# Capteur_Main_Droite.net
KiCad netlist of a schematic drawn in EasyEDA
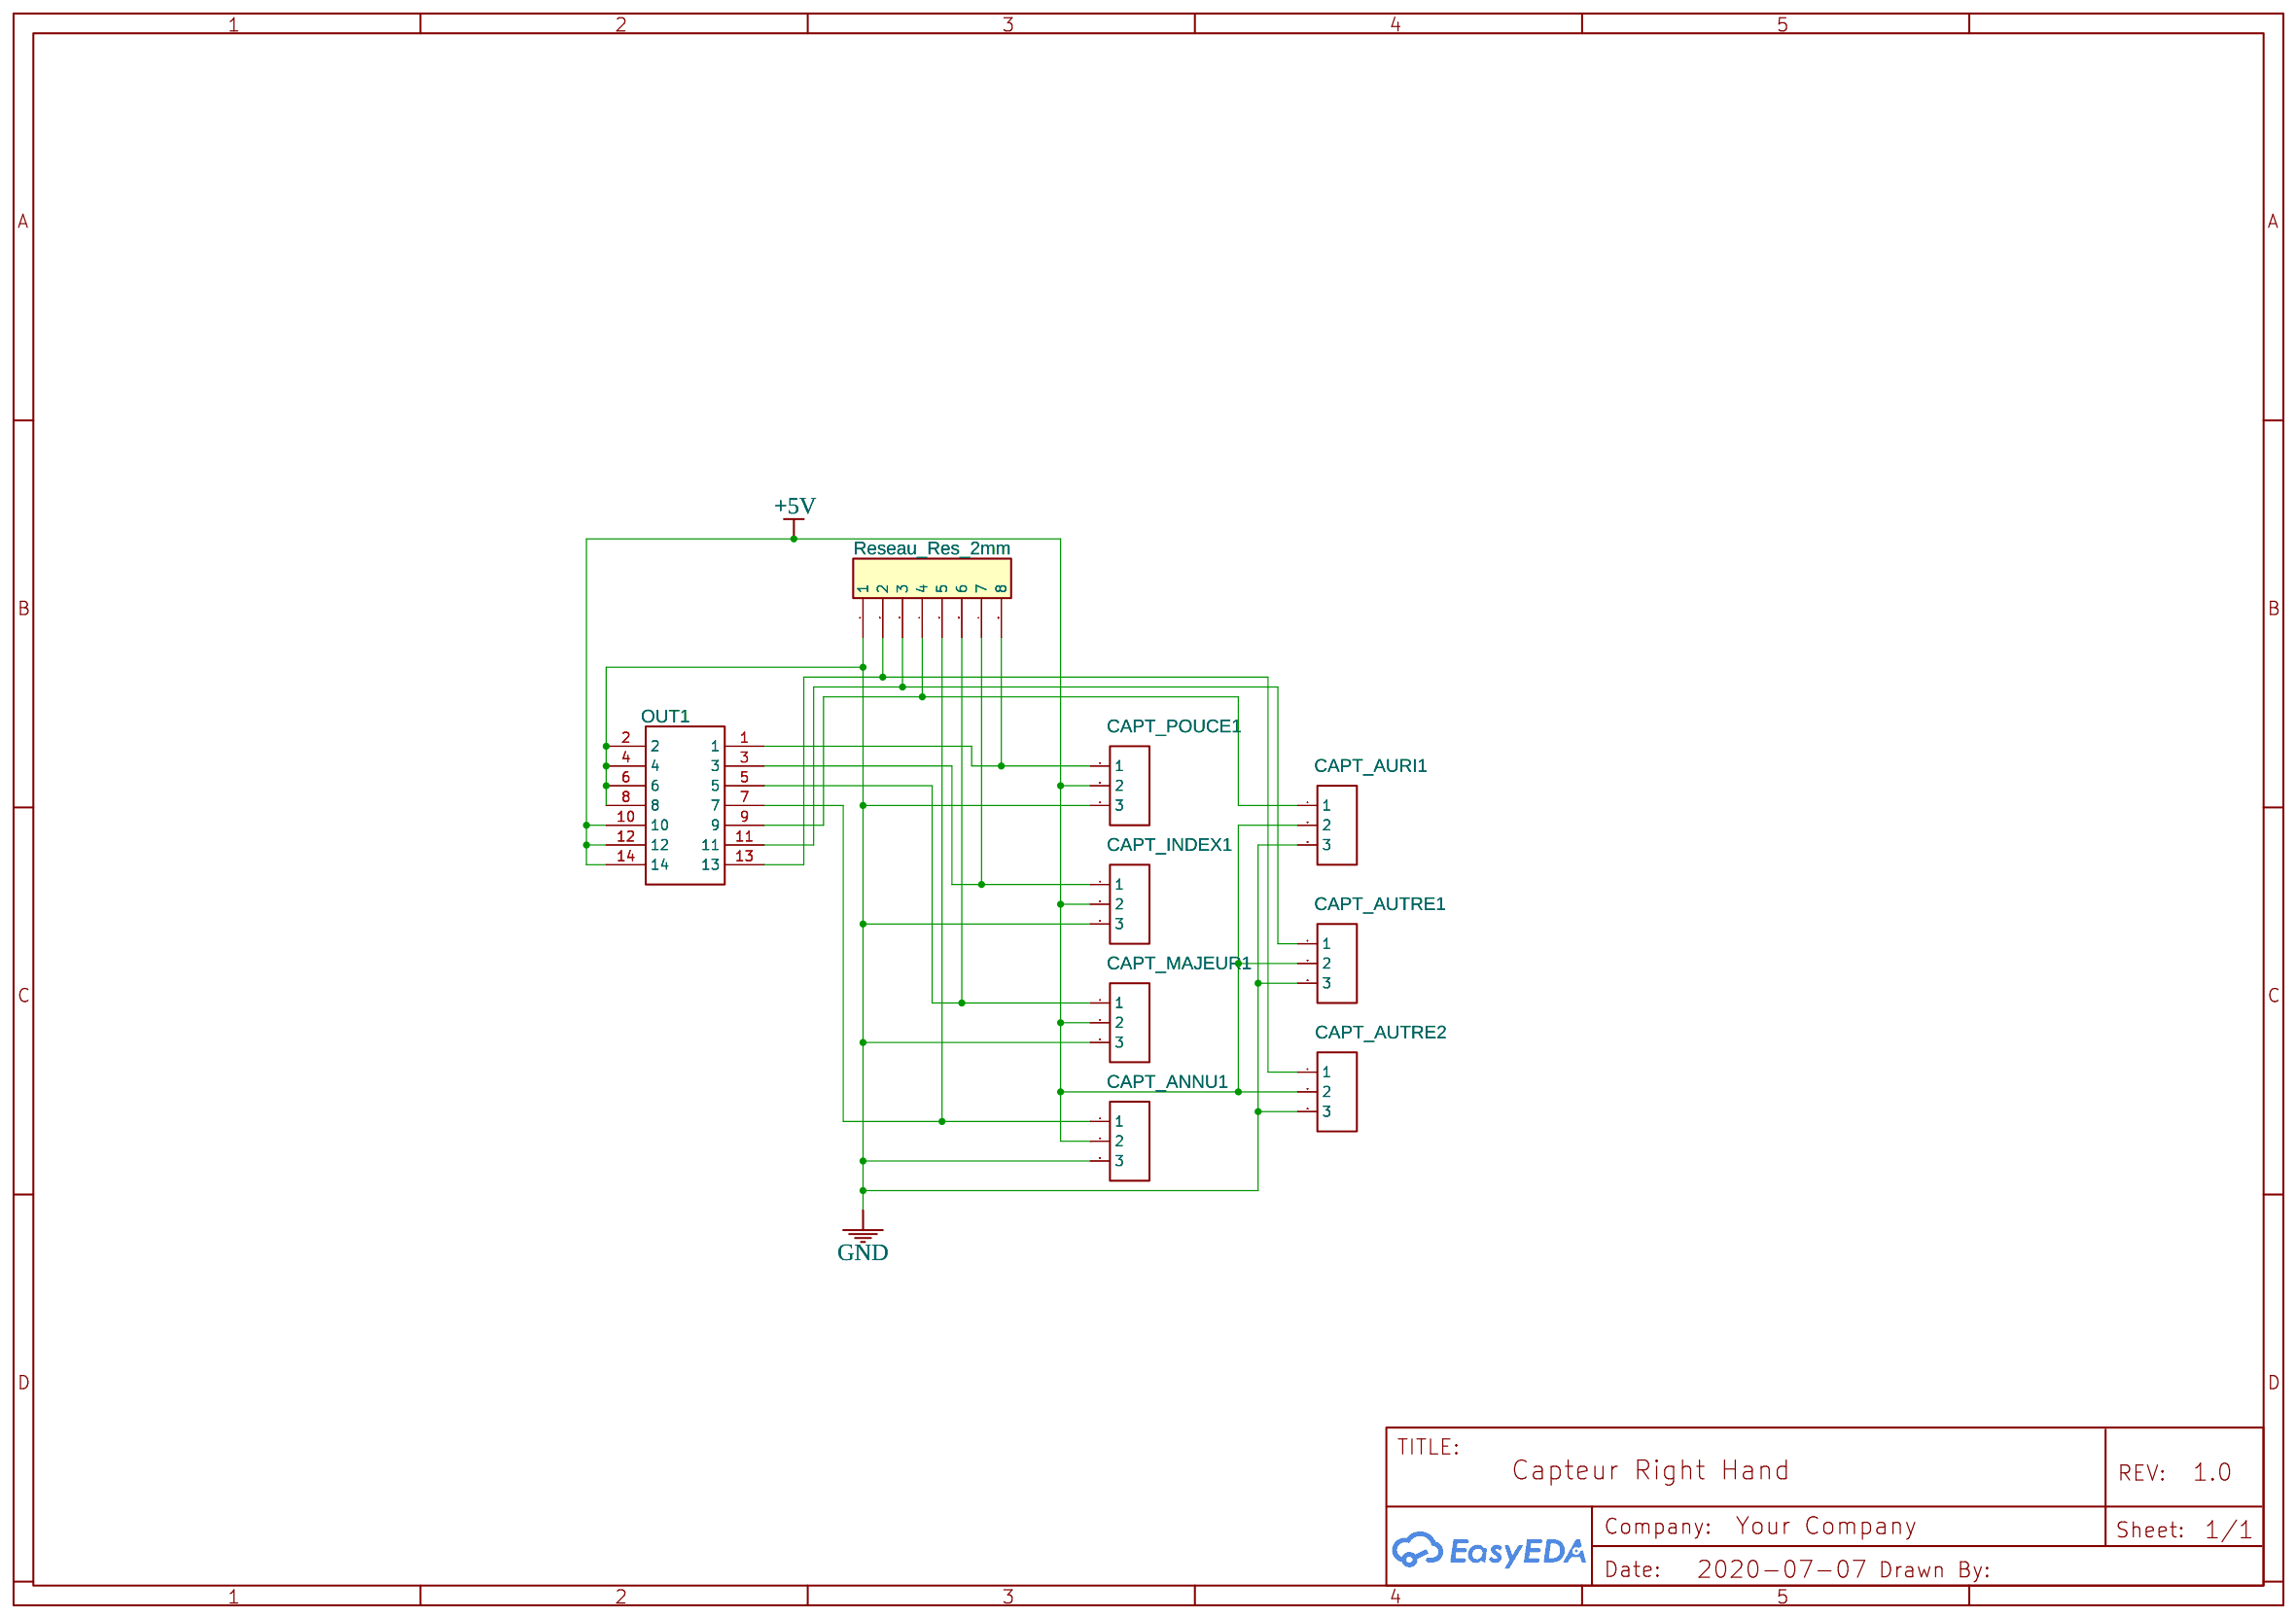
[diagram p0: schematic sheet]

(export (version "E")
  (design (tool "Eeschema 10.0.6"))
  (components
    (comp (ref "CAPT_ANNU1")
      (value "1")
      (fields
        (field (name "BOM_Manufacturer Part") "Header2.54mm 1*3P")
        (field (name "BOM_Supplier Part") "C49257")
      )
      (libsource (lib "") (part "Header-Male-2.54_1x3_4"))
    )
    (comp (ref "CAPT_AURI1")
      (value "1")
      (fields
        (field (name "BOM_Manufacturer Part") "Header2.54mm 1*3P")
        (field (name "BOM_Supplier Part") "C49257")
      )
      (libsource (lib "") (part "Header-Male-2.54_1x3_3"))
    )
    (comp (ref "CAPT_AUTRE1")
      (value "1")
      (fields
        (field (name "BOM_Manufacturer Part") "Header2.54mm 1*3P")
        (field (name "BOM_Supplier Part") "C49257")
      )
      (libsource (lib "") (part "Header-Male-2.54_1x3"))
    )
    (comp (ref "CAPT_AUTRE2")
      (value "1")
      (fields
        (field (name "BOM_Manufacturer Part") "Header2.54mm 1*3P")
        (field (name "BOM_Supplier Part") "C49257")
      )
      (libsource (lib "") (part "Header-Male-2.54_1x3"))
    )
    (comp (ref "CAPT_INDEX1")
      (value "1")
      (fields
        (field (name "BOM_Manufacturer Part") "Header2.54mm 1*3P")
        (field (name "BOM_Supplier Part") "C49257")
      )
      (libsource (lib "") (part "Header-Male-2.54_1x3_1"))
    )
    (comp (ref "CAPT_MAJEUR1")
      (value "1")
      (fields
        (field (name "BOM_Manufacturer Part") "Header2.54mm 1*3P")
        (field (name "BOM_Supplier Part") "C49257")
      )
      (libsource (lib "") (part "Header-Male-2.54_1x3_2"))
    )
    (comp (ref "CAPT_POUCE1")
      (value "1")
      (fields
        (field (name "BOM_Manufacturer Part") "Header2.54mm 1*3P")
        (field (name "BOM_Supplier Part") "C49257")
      )
      (libsource (lib "") (part "Header-Male-2.54_1x3_5"))
    )
    (comp (ref "OUT1")
      (value "Horn connector/2.0mm2*7P")
      (fields
        (field (name "BOM_Manufacturer Part") "Horn connector/2.0mm2*7P直简牛")
        (field (name "BOM_Supplier Part") "C29428")
      )
      (libsource (lib "") (part "Horn connector/2.0mm2*7P"))
    )
    (comp (ref "P1") (value "Reseau_Res_2mm") (libsource (lib "") (part "Reseau7R_2mm")))
  )
  (nets
    (net (code "1") (name "+5V") (class "Default")
      (node (ref "CAPT_ANNU1") (pin "2") (pinfunction "2_2") (pintype "input"))
      (node (ref "CAPT_AURI1") (pin "2") (pinfunction "2_2") (pintype "input"))
      (node (ref "CAPT_AUTRE1") (pin "2") (pinfunction "2_2") (pintype "input"))
      (node (ref "CAPT_AUTRE2") (pin "2") (pinfunction "2_2") (pintype "input"))
      (node (ref "CAPT_INDEX1") (pin "2") (pinfunction "2_2") (pintype "input"))
      (node (ref "CAPT_MAJEUR1") (pin "2") (pinfunction "2_2") (pintype "input"))
      (node (ref "CAPT_POUCE1") (pin "2") (pinfunction "2_2") (pintype "input"))
      (node (ref "OUT1") (pin "10") (pinfunction "10_10") (pintype "unspecified"))
      (node (ref "OUT1") (pin "12") (pinfunction "12_12") (pintype "unspecified"))
      (node (ref "OUT1") (pin "14") (pinfunction "14_14") (pintype "unspecified"))
    )
    (net (code "2") (name "GND") (class "Default")
      (node (ref "CAPT_ANNU1") (pin "3") (pinfunction "3_3") (pintype "input"))
      (node (ref "CAPT_AURI1") (pin "3") (pinfunction "3_3") (pintype "input"))
      (node (ref "CAPT_AUTRE1") (pin "3") (pinfunction "3_3") (pintype "input"))
      (node (ref "CAPT_AUTRE2") (pin "3") (pinfunction "3_3") (pintype "input"))
      (node (ref "CAPT_INDEX1") (pin "3") (pinfunction "3_3") (pintype "input"))
      (node (ref "CAPT_MAJEUR1") (pin "3") (pinfunction "3_3") (pintype "input"))
      (node (ref "CAPT_POUCE1") (pin "3") (pinfunction "3_3") (pintype "input"))
      (node (ref "OUT1") (pin "2") (pinfunction "2_2") (pintype "unspecified"))
      (node (ref "OUT1") (pin "4") (pinfunction "4_4") (pintype "unspecified"))
      (node (ref "OUT1") (pin "6") (pinfunction "6_6") (pintype "unspecified"))
      (node (ref "OUT1") (pin "8") (pinfunction "8_8") (pintype "unspecified"))
      (node (ref "P1") (pin "1") (pinfunction "1_1") (pintype "input"))
    )
    (net (code "3") (name "Net-(CAPT_ANNU1-Pad1)") (class "Default")
      (node (ref "CAPT_ANNU1") (pin "1") (pinfunction "1_1") (pintype "input"))
      (node (ref "OUT1") (pin "7") (pinfunction "7_7") (pintype "unspecified"))
      (node (ref "P1") (pin "5") (pinfunction "5_5") (pintype "input"))
    )
    (net (code "4") (name "Net-(CAPT_AURI1-Pad1)") (class "Default")
      (node (ref "CAPT_AURI1") (pin "1") (pinfunction "1_1") (pintype "input"))
      (node (ref "OUT1") (pin "9") (pinfunction "9_9") (pintype "unspecified"))
      (node (ref "P1") (pin "4") (pinfunction "4_4") (pintype "input"))
    )
    (net (code "5") (name "Net-(CAPT_AUTRE1-Pad1)") (class "Default")
      (node (ref "CAPT_AUTRE1") (pin "1") (pinfunction "1_1") (pintype "input"))
      (node (ref "OUT1") (pin "11") (pinfunction "11_11") (pintype "unspecified"))
      (node (ref "P1") (pin "3") (pinfunction "3_3") (pintype "input"))
    )
    (net (code "6") (name "Net-(CAPT_AUTRE2-Pad1)") (class "Default")
      (node (ref "CAPT_AUTRE2") (pin "1") (pinfunction "1_1") (pintype "input"))
      (node (ref "OUT1") (pin "13") (pinfunction "13_13") (pintype "unspecified"))
      (node (ref "P1") (pin "2") (pinfunction "2_2") (pintype "input"))
    )
    (net (code "7") (name "Net-(CAPT_INDEX1-Pad1)") (class "Default")
      (node (ref "CAPT_INDEX1") (pin "1") (pinfunction "1_1") (pintype "input"))
      (node (ref "OUT1") (pin "3") (pinfunction "3_3") (pintype "unspecified"))
      (node (ref "P1") (pin "7") (pinfunction "7_7") (pintype "input"))
    )
    (net (code "8") (name "Net-(CAPT_MAJEUR1-Pad1)") (class "Default")
      (node (ref "CAPT_MAJEUR1") (pin "1") (pinfunction "1_1") (pintype "input"))
      (node (ref "OUT1") (pin "5") (pinfunction "5_5") (pintype "unspecified"))
      (node (ref "P1") (pin "6") (pinfunction "6_6") (pintype "input"))
    )
    (net (code "9") (name "Net-(CAPT_POUCE1-Pad1)") (class "Default")
      (node (ref "CAPT_POUCE1") (pin "1") (pinfunction "1_1") (pintype "input"))
      (node (ref "OUT1") (pin "1") (pinfunction "1_1") (pintype "unspecified"))
      (node (ref "P1") (pin "8") (pinfunction "8_8") (pintype "input"))
    )
  )
)
